# ADC_Filter_Cell.net
KiCad netlist of a schematic drawn in Altium Designer
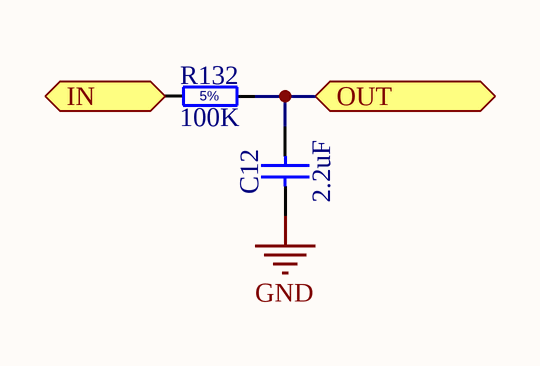
[diagram p0: ADC_Filter_Cell.SchDoc]

(export (version "E")
  (design (tool "Eeschema 10.0.6"))
  (components
    (comp (ref "C12")
      (value "2.2uF")
      (footprint "CAPRR254-254X381X508")
      (description "Non-polarised capacitor")
      (fields
        (field (name "PART NUMBER") "CCR_15PF_100V_5%_COG_254-254X381X508")
        (field (name "VOLTAGE") "100VDC")
        (field (name "AUTHOR") "CERN DEM JLC")
      )
      (libsource (lib "Capacitors") (part "Capacitor - non polarized"))
    )
    (comp (ref "R132")
      (value "100K")
      (footprint "RES_ARCOL_RCC025")
      (description "Resistor - 5%")
      (fields
        (field (name "PART NUMBER") "RCF_5K1_5%_0.25W_+10-6PPM_ARCOL_RCC025")
        (field (name "POWER") "0.25W")
        (field (name "AUTHOR") "CERN DEM JLC")
      )
      (libsource (lib "Resistors") (part "Resistor - 5%"))
    )
  )
  (nets
    (net (code "1") (name "/IN") (class "Default")
      (node (ref "R132") (pin "1") (pinfunction "1_1") (pintype "passive"))
    )
    (net (code "2") (name "/OUT") (class "Default")
      (node (ref "C12") (pin "2") (pinfunction "2_2") (pintype "passive"))
      (node (ref "R132") (pin "2") (pinfunction "2_2") (pintype "passive"))
    )
    (net (code "3") (name "GND") (class "Default")
      (node (ref "C12") (pin "1") (pinfunction "1_1") (pintype "passive"))
    )
  )
)
